# MPBoard_L2_Relay1_ext.net
KiCad netlist of a schematic drawn in Altium Designer
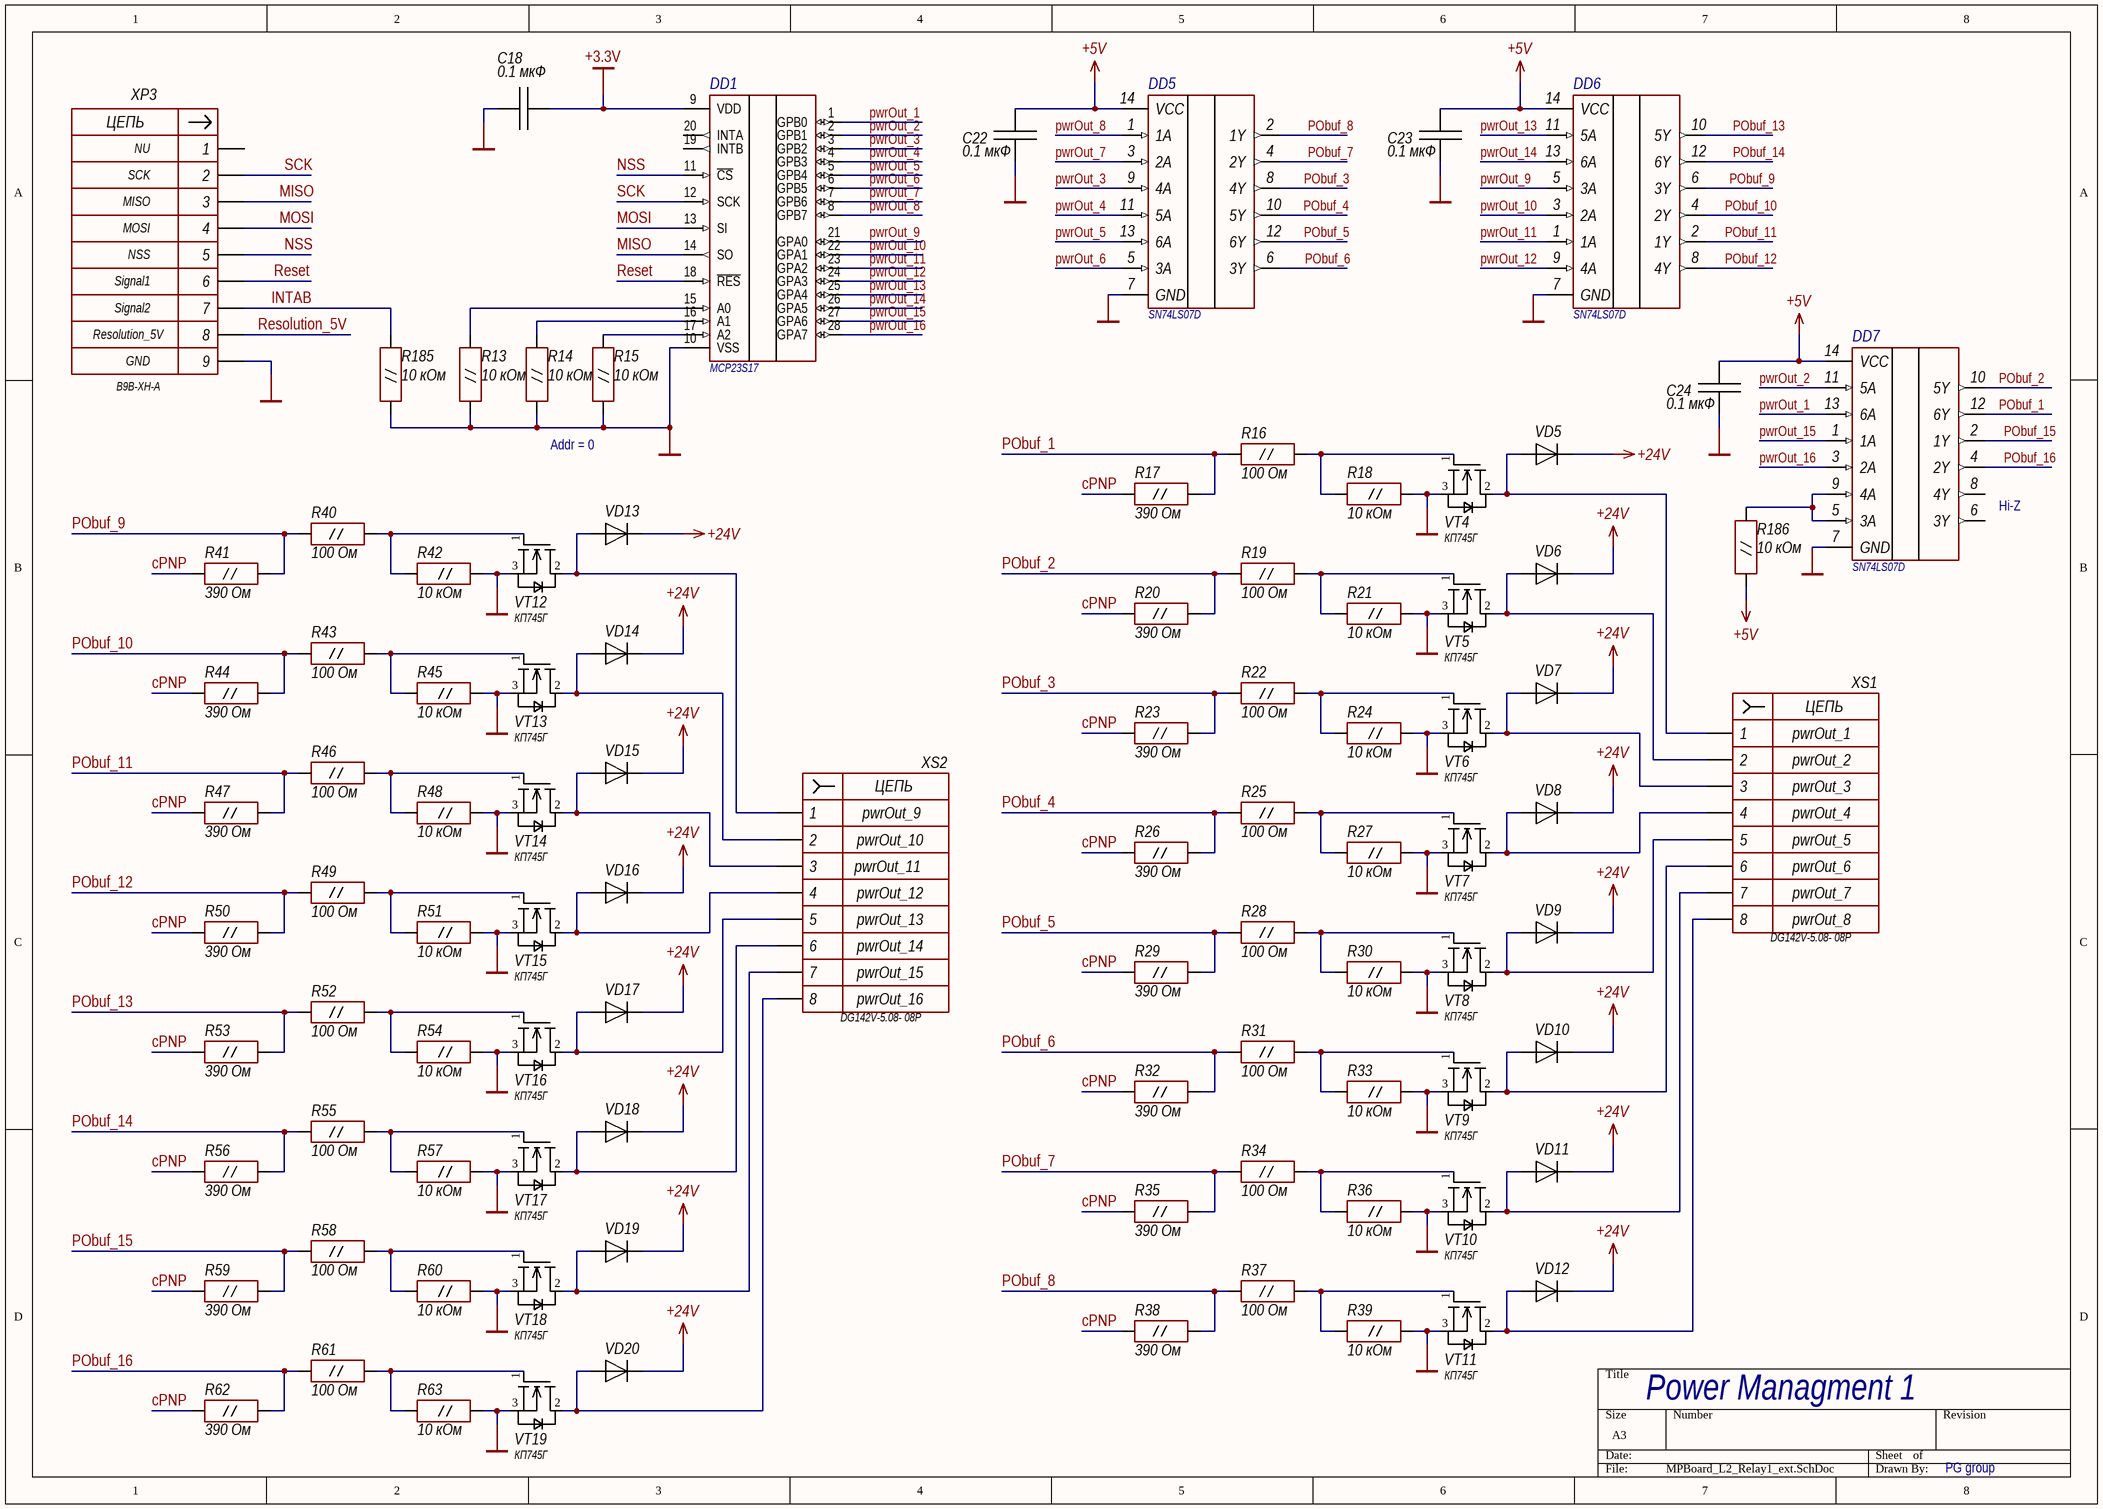
[diagram p0: MPBoard_L2_Relay1_ext.SchDoc]

(export (version "E")
  (design (tool "Eeschema 10.0.6"))
  (components
    (comp (ref "C18")
      (value "0.1 мкФ")
      (footprint "CAP-0603")
      (description "Конденсатор")
      (fields (field (name "MF") "KEMET") (field (name "TOLERANCE") "± 10 %"))
      (libsource (lib "MainBoard") (part "C"))
    )
    (comp (ref "C22")
      (value "0.1 мкФ")
      (footprint "CAP-0603")
      (description "Конденсатор")
      (fields (field (name "MF") "KEMET") (field (name "TOLERANCE") "± 10 %"))
      (libsource (lib "MainBoard") (part "C"))
    )
    (comp (ref "C23")
      (value "0.1 мкФ")
      (footprint "CAP-0603")
      (description "Конденсатор")
      (fields (field (name "MF") "KEMET") (field (name "TOLERANCE") "± 10 %"))
      (libsource (lib "MainBoard") (part "C"))
    )
    (comp (ref "C24")
      (value "0.1 мкФ")
      (footprint "CAP-0603")
      (description "Конденсатор")
      (fields (field (name "MF") "KEMET") (field (name "TOLERANCE") "± 10 %"))
      (libsource (lib "MainBoard") (part "C"))
    )
    (comp (ref "DD1")
      (value "MCP23S17")
      (footprint "SOIC-28")
      (description "I/O Expander 16 SPI")
      (fields (field (name "MF") "Microchip"))
      (libsource (lib "MPBoard") (part "DD_MCP23S17"))
    )
    (comp (ref "DD5")
      (value "SN74LS07D")
      (footprint "SOIC-14")
      (description "6-ch, 4.75_5.25V bipolar buffers with OC outputs")
      (fields (field (name "MF") "Texas Instruments"))
      (libsource (lib "MPBoard") (part "DD_SN74LS07D"))
    )
    (comp (ref "DD6")
      (value "SN74LS07D")
      (footprint "SOIC-14")
      (description "6-ch, 4.75_5.25V bipolar buffers with OC outputs")
      (fields (field (name "MF") "Texas Instruments"))
      (libsource (lib "") (part "DD_SN74LS07D_2"))
    )
    (comp (ref "DD7")
      (value "SN74LS07D")
      (footprint "SOIC-14")
      (description "6-ch, 4.75_5.25V bipolar buffers with OC outputs")
      (fields (field (name "MF") "Texas Instruments"))
      (libsource (lib "") (part "DD_SN74LS07D_1"))
    )
    (comp (ref "R13")
      (value "10 кОм")
      (footprint "RES-0603")
      (description "Резистор 0.1 W")
      (fields (field (name "MF") "Vishay") (field (name "TOLERANCE") "± 1 %"))
      (libsource (lib "") (part "R_0.125W_2"))
    )
    (comp (ref "R14")
      (value "10 кОм")
      (footprint "RES-0603")
      (description "Резистор 0.1 W")
      (fields (field (name "MF") "Vishay") (field (name "TOLERANCE") "± 1 %"))
      (libsource (lib "") (part "R_0.125W_2"))
    )
    (comp (ref "R15")
      (value "10 кОм")
      (footprint "RES-0603")
      (description "Резистор 0.1 W")
      (fields (field (name "MF") "Vishay") (field (name "TOLERANCE") "± 1 %"))
      (libsource (lib "") (part "R_0.125W_2"))
    )
    (comp (ref "R16")
      (value "100 Ом")
      (footprint "RES-0805")
      (description "Резистор 0.125 W")
      (fields (field (name "MF") "Vishay") (field (name "TOLERANCE") "± 1 %"))
      (libsource (lib "MainBoard") (part "R_0.125W"))
    )
    (comp (ref "R17")
      (value "390 Ом")
      (footprint "RES-0805")
      (description "Резистор 0.125 W")
      (fields (field (name "MF") "Vishay") (field (name "TOLERANCE") "± 1 %"))
      (libsource (lib "MainBoard") (part "R_0.125W"))
    )
    (comp (ref "R18")
      (value "10 кОм")
      (footprint "RES-0805")
      (description "Резистор 0.125 W")
      (fields (field (name "MF") "Vishay") (field (name "TOLERANCE") "± 1 %"))
      (libsource (lib "") (part "R_0.125W_1"))
    )
    (comp (ref "R19")
      (value "100 Ом")
      (footprint "RES-0805")
      (description "Резистор 0.125 W")
      (fields (field (name "MF") "Vishay") (field (name "TOLERANCE") "± 1 %"))
      (libsource (lib "MainBoard") (part "R_0.125W"))
    )
    (comp (ref "R20")
      (value "390 Ом")
      (footprint "RES-0805")
      (description "Резистор 0.125 W")
      (fields (field (name "MF") "Vishay") (field (name "TOLERANCE") "± 1 %"))
      (libsource (lib "MainBoard") (part "R_0.125W"))
    )
    (comp (ref "R21")
      (value "10 кОм")
      (footprint "RES-0805")
      (description "Резистор 0.125 W")
      (fields (field (name "MF") "Vishay") (field (name "TOLERANCE") "± 1 %"))
      (libsource (lib "") (part "R_0.125W_1"))
    )
    (comp (ref "R22")
      (value "100 Ом")
      (footprint "RES-0805")
      (description "Резистор 0.125 W")
      (fields (field (name "MF") "Vishay") (field (name "TOLERANCE") "± 1 %"))
      (libsource (lib "MainBoard") (part "R_0.125W"))
    )
    (comp (ref "R23")
      (value "390 Ом")
      (footprint "RES-0805")
      (description "Резистор 0.125 W")
      (fields (field (name "MF") "Vishay") (field (name "TOLERANCE") "± 1 %"))
      (libsource (lib "MainBoard") (part "R_0.125W"))
    )
    (comp (ref "R24")
      (value "10 кОм")
      (footprint "RES-0805")
      (description "Резистор 0.125 W")
      (fields (field (name "MF") "Vishay") (field (name "TOLERANCE") "± 1 %"))
      (libsource (lib "") (part "R_0.125W_1"))
    )
    (comp (ref "R25")
      (value "100 Ом")
      (footprint "RES-0805")
      (description "Резистор 0.125 W")
      (fields (field (name "MF") "Vishay") (field (name "TOLERANCE") "± 1 %"))
      (libsource (lib "MainBoard") (part "R_0.125W"))
    )
    (comp (ref "R26")
      (value "390 Ом")
      (footprint "RES-0805")
      (description "Резистор 0.125 W")
      (fields (field (name "MF") "Vishay") (field (name "TOLERANCE") "± 1 %"))
      (libsource (lib "MainBoard") (part "R_0.125W"))
    )
    (comp (ref "R27")
      (value "10 кОм")
      (footprint "RES-0805")
      (description "Резистор 0.125 W")
      (fields (field (name "MF") "Vishay") (field (name "TOLERANCE") "± 1 %"))
      (libsource (lib "") (part "R_0.125W_1"))
    )
    (comp (ref "R28")
      (value "100 Ом")
      (footprint "RES-0805")
      (description "Резистор 0.125 W")
      (fields (field (name "MF") "Vishay") (field (name "TOLERANCE") "± 1 %"))
      (libsource (lib "MainBoard") (part "R_0.125W"))
    )
    (comp (ref "R29")
      (value "390 Ом")
      (footprint "RES-0805")
      (description "Резистор 0.125 W")
      (fields (field (name "MF") "Vishay") (field (name "TOLERANCE") "± 1 %"))
      (libsource (lib "MainBoard") (part "R_0.125W"))
    )
    (comp (ref "R30")
      (value "10 кОм")
      (footprint "RES-0805")
      (description "Резистор 0.125 W")
      (fields (field (name "MF") "Vishay") (field (name "TOLERANCE") "± 1 %"))
      (libsource (lib "") (part "R_0.125W_1"))
    )
    (comp (ref "R31")
      (value "100 Ом")
      (footprint "RES-0805")
      (description "Резистор 0.125 W")
      (fields (field (name "MF") "Vishay") (field (name "TOLERANCE") "± 1 %"))
      (libsource (lib "MainBoard") (part "R_0.125W"))
    )
    (comp (ref "R32")
      (value "390 Ом")
      (footprint "RES-0805")
      (description "Резистор 0.125 W")
      (fields (field (name "MF") "Vishay") (field (name "TOLERANCE") "± 1 %"))
      (libsource (lib "MainBoard") (part "R_0.125W"))
    )
    (comp (ref "R33")
      (value "10 кОм")
      (footprint "RES-0805")
      (description "Резистор 0.125 W")
      (fields (field (name "MF") "Vishay") (field (name "TOLERANCE") "± 1 %"))
      (libsource (lib "") (part "R_0.125W_1"))
    )
    (comp (ref "R34")
      (value "100 Ом")
      (footprint "RES-0805")
      (description "Резистор 0.125 W")
      (fields (field (name "MF") "Vishay") (field (name "TOLERANCE") "± 1 %"))
      (libsource (lib "MainBoard") (part "R_0.125W"))
    )
    (comp (ref "R35")
      (value "390 Ом")
      (footprint "RES-0805")
      (description "Резистор 0.125 W")
      (fields (field (name "MF") "Vishay") (field (name "TOLERANCE") "± 1 %"))
      (libsource (lib "MainBoard") (part "R_0.125W"))
    )
    (comp (ref "R36")
      (value "10 кОм")
      (footprint "RES-0805")
      (description "Резистор 0.125 W")
      (fields (field (name "MF") "Vishay") (field (name "TOLERANCE") "± 1 %"))
      (libsource (lib "") (part "R_0.125W_1"))
    )
    (comp (ref "R37")
      (value "100 Ом")
      (footprint "RES-0805")
      (description "Резистор 0.125 W")
      (fields (field (name "MF") "Vishay") (field (name "TOLERANCE") "± 1 %"))
      (libsource (lib "MainBoard") (part "R_0.125W"))
    )
    (comp (ref "R38")
      (value "390 Ом")
      (footprint "RES-0805")
      (description "Резистор 0.125 W")
      (fields (field (name "MF") "Vishay") (field (name "TOLERANCE") "± 1 %"))
      (libsource (lib "MainBoard") (part "R_0.125W"))
    )
    (comp (ref "R39")
      (value "10 кОм")
      (footprint "RES-0805")
      (description "Резистор 0.125 W")
      (fields (field (name "MF") "Vishay") (field (name "TOLERANCE") "± 1 %"))
      (libsource (lib "") (part "R_0.125W_1"))
    )
    (comp (ref "R40")
      (value "100 Ом")
      (footprint "RES-0805")
      (description "Резистор 0.125 W")
      (fields (field (name "MF") "Vishay") (field (name "TOLERANCE") "± 1 %"))
      (libsource (lib "MainBoard") (part "R_0.125W"))
    )
    (comp (ref "R41")
      (value "390 Ом")
      (footprint "RES-0805")
      (description "Резистор 0.125 W")
      (fields (field (name "MF") "Vishay") (field (name "TOLERANCE") "± 1 %"))
      (libsource (lib "MainBoard") (part "R_0.125W"))
    )
    (comp (ref "R42")
      (value "10 кОм")
      (footprint "RES-0805")
      (description "Резистор 0.125 W")
      (fields (field (name "MF") "Vishay") (field (name "TOLERANCE") "± 1 %"))
      (libsource (lib "") (part "R_0.125W_1"))
    )
    (comp (ref "R43")
      (value "100 Ом")
      (footprint "RES-0805")
      (description "Резистор 0.125 W")
      (fields (field (name "MF") "Vishay") (field (name "TOLERANCE") "± 1 %"))
      (libsource (lib "MainBoard") (part "R_0.125W"))
    )
    (comp (ref "R44")
      (value "390 Ом")
      (footprint "RES-0805")
      (description "Резистор 0.125 W")
      (fields (field (name "MF") "Vishay") (field (name "TOLERANCE") "± 1 %"))
      (libsource (lib "MainBoard") (part "R_0.125W"))
    )
    (comp (ref "R45")
      (value "10 кОм")
      (footprint "RES-0805")
      (description "Резистор 0.125 W")
      (fields (field (name "MF") "Vishay") (field (name "TOLERANCE") "± 1 %"))
      (libsource (lib "") (part "R_0.125W_1"))
    )
    (comp (ref "R46")
      (value "100 Ом")
      (footprint "RES-0805")
      (description "Резистор 0.125 W")
      (fields (field (name "MF") "Vishay") (field (name "TOLERANCE") "± 1 %"))
      (libsource (lib "MainBoard") (part "R_0.125W"))
    )
    (comp (ref "R47")
      (value "390 Ом")
      (footprint "RES-0805")
      (description "Резистор 0.125 W")
      (fields (field (name "MF") "Vishay") (field (name "TOLERANCE") "± 1 %"))
      (libsource (lib "MainBoard") (part "R_0.125W"))
    )
    (comp (ref "R48")
      (value "10 кОм")
      (footprint "RES-0805")
      (description "Резистор 0.125 W")
      (fields (field (name "MF") "Vishay") (field (name "TOLERANCE") "± 1 %"))
      (libsource (lib "") (part "R_0.125W_1"))
    )
    (comp (ref "R49")
      (value "100 Ом")
      (footprint "RES-0805")
      (description "Резистор 0.125 W")
      (fields (field (name "MF") "Vishay") (field (name "TOLERANCE") "± 1 %"))
      (libsource (lib "MainBoard") (part "R_0.125W"))
    )
    (comp (ref "R50")
      (value "390 Ом")
      (footprint "RES-0805")
      (description "Резистор 0.125 W")
      (fields (field (name "MF") "Vishay") (field (name "TOLERANCE") "± 1 %"))
      (libsource (lib "MainBoard") (part "R_0.125W"))
    )
    (comp (ref "R51")
      (value "10 кОм")
      (footprint "RES-0805")
      (description "Резистор 0.125 W")
      (fields (field (name "MF") "Vishay") (field (name "TOLERANCE") "± 1 %"))
      (libsource (lib "") (part "R_0.125W_1"))
    )
    (comp (ref "R52")
      (value "100 Ом")
      (footprint "RES-0805")
      (description "Резистор 0.125 W")
      (fields (field (name "MF") "Vishay") (field (name "TOLERANCE") "± 1 %"))
      (libsource (lib "MainBoard") (part "R_0.125W"))
    )
    (comp (ref "R53")
      (value "390 Ом")
      (footprint "RES-0805")
      (description "Резистор 0.125 W")
      (fields (field (name "MF") "Vishay") (field (name "TOLERANCE") "± 1 %"))
      (libsource (lib "MainBoard") (part "R_0.125W"))
    )
    (comp (ref "R54")
      (value "10 кОм")
      (footprint "RES-0805")
      (description "Резистор 0.125 W")
      (fields (field (name "MF") "Vishay") (field (name "TOLERANCE") "± 1 %"))
      (libsource (lib "") (part "R_0.125W_1"))
    )
    (comp (ref "R55")
      (value "100 Ом")
      (footprint "RES-0805")
      (description "Резистор 0.125 W")
      (fields (field (name "MF") "Vishay") (field (name "TOLERANCE") "± 1 %"))
      (libsource (lib "MainBoard") (part "R_0.125W"))
    )
    (comp (ref "R56")
      (value "390 Ом")
      (footprint "RES-0805")
      (description "Резистор 0.125 W")
      (fields (field (name "MF") "Vishay") (field (name "TOLERANCE") "± 1 %"))
      (libsource (lib "MainBoard") (part "R_0.125W"))
    )
    (comp (ref "R57")
      (value "10 кОм")
      (footprint "RES-0805")
      (description "Резистор 0.125 W")
      (fields (field (name "MF") "Vishay") (field (name "TOLERANCE") "± 1 %"))
      (libsource (lib "") (part "R_0.125W_1"))
    )
    (comp (ref "R58")
      (value "100 Ом")
      (footprint "RES-0805")
      (description "Резистор 0.125 W")
      (fields (field (name "MF") "Vishay") (field (name "TOLERANCE") "± 1 %"))
      (libsource (lib "MainBoard") (part "R_0.125W"))
    )
    (comp (ref "R59")
      (value "390 Ом")
      (footprint "RES-0805")
      (description "Резистор 0.125 W")
      (fields (field (name "MF") "Vishay") (field (name "TOLERANCE") "± 1 %"))
      (libsource (lib "MainBoard") (part "R_0.125W"))
    )
    (comp (ref "R60")
      (value "10 кОм")
      (footprint "RES-0805")
      (description "Резистор 0.125 W")
      (fields (field (name "MF") "Vishay") (field (name "TOLERANCE") "± 1 %"))
      (libsource (lib "") (part "R_0.125W_1"))
    )
    (comp (ref "R61")
      (value "100 Ом")
      (footprint "RES-0805")
      (description "Резистор 0.125 W")
      (fields (field (name "MF") "Vishay") (field (name "TOLERANCE") "± 1 %"))
      (libsource (lib "MainBoard") (part "R_0.125W"))
    )
    (comp (ref "R62")
      (value "390 Ом")
      (footprint "RES-0805")
      (description "Резистор 0.125 W")
      (fields (field (name "MF") "Vishay") (field (name "TOLERANCE") "± 1 %"))
      (libsource (lib "MainBoard") (part "R_0.125W"))
    )
    (comp (ref "R63")
      (value "10 кОм")
      (footprint "RES-0805")
      (description "Резистор 0.125 W")
      (fields (field (name "MF") "Vishay") (field (name "TOLERANCE") "± 1 %"))
      (libsource (lib "") (part "R_0.125W_1"))
    )
    (comp (ref "R185")
      (value "10 кОм")
      (footprint "RES-0603")
      (description "Резистор 0.1 W")
      (fields (field (name "MF") "Vishay") (field (name "TOLERANCE") "± 1 %"))
      (libsource (lib "") (part "R_0.125W_2"))
    )
    (comp (ref "R186")
      (value "10 кОм")
      (footprint "RES-0603")
      (description "Резистор 0.1 W")
      (fields (field (name "MF") "Vishay") (field (name "TOLERANCE") "± 1 %"))
      (libsource (lib "") (part "R_0.125W_2"))
    )
    (comp (ref "VD5")
      (value "HER108")
      (footprint "DIOD-MILS-400")
      (description "Диод Выпрямительный")
      (fields (field (name "MF") "Taiwan Semiconductor") (field (name "MFPARTNUM") "HER108G"))
      (libsource (lib "MainBoard") (part "VD"))
    )
    (comp (ref "VD6")
      (value "HER108")
      (footprint "DIOD-MILS-400")
      (description "Диод Выпрямительный")
      (fields (field (name "MF") "Taiwan Semiconductor") (field (name "MFPARTNUM") "HER108G"))
      (libsource (lib "MainBoard") (part "VD"))
    )
    (comp (ref "VD7")
      (value "HER108")
      (footprint "DIOD-MILS-400")
      (description "Диод Выпрямительный")
      (fields (field (name "MF") "Taiwan Semiconductor") (field (name "MFPARTNUM") "HER108G"))
      (libsource (lib "MainBoard") (part "VD"))
    )
    (comp (ref "VD8")
      (value "HER108")
      (footprint "DIOD-MILS-400")
      (description "Диод Выпрямительный")
      (fields (field (name "MF") "Taiwan Semiconductor") (field (name "MFPARTNUM") "HER108G"))
      (libsource (lib "MainBoard") (part "VD"))
    )
    (comp (ref "VD9")
      (value "HER108")
      (footprint "DIOD-MILS-400")
      (description "Диод Выпрямительный")
      (fields (field (name "MF") "Taiwan Semiconductor") (field (name "MFPARTNUM") "HER108G"))
      (libsource (lib "MainBoard") (part "VD"))
    )
    (comp (ref "VD10")
      (value "HER108")
      (footprint "DIOD-MILS-400")
      (description "Диод Выпрямительный")
      (fields (field (name "MF") "Taiwan Semiconductor") (field (name "MFPARTNUM") "HER108G"))
      (libsource (lib "MainBoard") (part "VD"))
    )
    (comp (ref "VD11")
      (value "HER108")
      (footprint "DIOD-MILS-400")
      (description "Диод Выпрямительный")
      (fields (field (name "MF") "Taiwan Semiconductor") (field (name "MFPARTNUM") "HER108G"))
      (libsource (lib "MainBoard") (part "VD"))
    )
    (comp (ref "VD12")
      (value "HER108")
      (footprint "DIOD-MILS-400")
      (description "Диод Выпрямительный")
      (fields (field (name "MF") "Taiwan Semiconductor") (field (name "MFPARTNUM") "HER108G"))
      (libsource (lib "MainBoard") (part "VD"))
    )
    (comp (ref "VD13")
      (value "HER108")
      (footprint "DIOD-MILS-400")
      (description "Диод Выпрямительный")
      (fields (field (name "MF") "Taiwan Semiconductor") (field (name "MFPARTNUM") "HER108G"))
      (libsource (lib "MainBoard") (part "VD"))
    )
    (comp (ref "VD14")
      (value "HER108")
      (footprint "DIOD-MILS-400")
      (description "Диод Выпрямительный")
      (fields (field (name "MF") "Taiwan Semiconductor") (field (name "MFPARTNUM") "HER108G"))
      (libsource (lib "MainBoard") (part "VD"))
    )
    (comp (ref "VD15")
      (value "HER108")
      (footprint "DIOD-MILS-400")
      (description "Диод Выпрямительный")
      (fields (field (name "MF") "Taiwan Semiconductor") (field (name "MFPARTNUM") "HER108G"))
      (libsource (lib "MainBoard") (part "VD"))
    )
    (comp (ref "VD16")
      (value "HER108")
      (footprint "DIOD-MILS-400")
      (description "Диод Выпрямительный")
      (fields (field (name "MF") "Taiwan Semiconductor") (field (name "MFPARTNUM") "HER108G"))
      (libsource (lib "MainBoard") (part "VD"))
    )
    (comp (ref "VD17")
      (value "HER108")
      (footprint "DIOD-MILS-400")
      (description "Диод Выпрямительный")
      (fields (field (name "MF") "Taiwan Semiconductor") (field (name "MFPARTNUM") "HER108G"))
      (libsource (lib "MainBoard") (part "VD"))
    )
    (comp (ref "VD18")
      (value "HER108")
      (footprint "DIOD-MILS-400")
      (description "Диод Выпрямительный")
      (fields (field (name "MF") "Taiwan Semiconductor") (field (name "MFPARTNUM") "HER108G"))
      (libsource (lib "MainBoard") (part "VD"))
    )
    (comp (ref "VD19")
      (value "HER108")
      (footprint "DIOD-MILS-400")
      (description "Диод Выпрямительный")
      (fields (field (name "MF") "Taiwan Semiconductor") (field (name "MFPARTNUM") "HER108G"))
      (libsource (lib "MainBoard") (part "VD"))
    )
    (comp (ref "VD20")
      (value "HER108")
      (footprint "DIOD-MILS-400")
      (description "Диод Выпрямительный")
      (fields (field (name "MF") "Taiwan Semiconductor") (field (name "MFPARTNUM") "HER108G"))
      (libsource (lib "MainBoard") (part "VD"))
    )
    (comp (ref "VT4")
      (value "КП745Г")
      (footprint "TO220S inline")
      (description "MOSFET")
      (fields (field (name "MF") "Интеграл") (field (name "VOLTAGE") "100 В"))
      (libsource (lib "MPBoard") (part "VT_N-MOSFET"))
    )
    (comp (ref "VT5")
      (value "КП745Г")
      (footprint "TO220S inline")
      (description "MOSFET")
      (fields (field (name "MF") "Интеграл") (field (name "VOLTAGE") "100 В"))
      (libsource (lib "MPBoard") (part "VT_N-MOSFET"))
    )
    (comp (ref "VT6")
      (value "КП745Г")
      (footprint "TO220S inline")
      (description "MOSFET")
      (fields (field (name "MF") "Интеграл") (field (name "VOLTAGE") "100 В"))
      (libsource (lib "MPBoard") (part "VT_N-MOSFET"))
    )
    (comp (ref "VT7")
      (value "КП745Г")
      (footprint "TO220S inline")
      (description "MOSFET")
      (fields (field (name "MF") "Интеграл") (field (name "VOLTAGE") "100 В"))
      (libsource (lib "MPBoard") (part "VT_N-MOSFET"))
    )
    (comp (ref "VT8")
      (value "КП745Г")
      (footprint "TO220S inline")
      (description "MOSFET")
      (fields (field (name "MF") "Интеграл") (field (name "VOLTAGE") "100 В"))
      (libsource (lib "MPBoard") (part "VT_N-MOSFET"))
    )
    (comp (ref "VT9")
      (value "КП745Г")
      (footprint "TO220S inline")
      (description "MOSFET")
      (fields (field (name "MF") "Интеграл") (field (name "VOLTAGE") "100 В"))
      (libsource (lib "MPBoard") (part "VT_N-MOSFET"))
    )
    (comp (ref "VT10")
      (value "КП745Г")
      (footprint "TO220S inline")
      (description "MOSFET")
      (fields (field (name "MF") "Интеграл") (field (name "VOLTAGE") "100 В"))
      (libsource (lib "MPBoard") (part "VT_N-MOSFET"))
    )
    (comp (ref "VT11")
      (value "КП745Г")
      (footprint "TO220S inline")
      (description "MOSFET")
      (fields (field (name "MF") "Интеграл") (field (name "VOLTAGE") "100 В"))
      (libsource (lib "MPBoard") (part "VT_N-MOSFET"))
    )
    (comp (ref "VT12")
      (value "КП745Г")
      (footprint "TO220S inline")
      (description "MOSFET")
      (fields (field (name "MF") "Интеграл") (field (name "VOLTAGE") "100 В"))
      (libsource (lib "MPBoard") (part "VT_N-MOSFET"))
    )
    (comp (ref "VT13")
      (value "КП745Г")
      (footprint "TO220S inline")
      (description "MOSFET")
      (fields (field (name "MF") "Интеграл") (field (name "VOLTAGE") "100 В"))
      (libsource (lib "MPBoard") (part "VT_N-MOSFET"))
    )
    (comp (ref "VT14")
      (value "КП745Г")
      (footprint "TO220S inline")
      (description "MOSFET")
      (fields (field (name "MF") "Интеграл") (field (name "VOLTAGE") "100 В"))
      (libsource (lib "MPBoard") (part "VT_N-MOSFET"))
    )
    (comp (ref "VT15")
      (value "КП745Г")
      (footprint "TO220S inline")
      (description "MOSFET")
      (fields (field (name "MF") "Интеграл") (field (name "VOLTAGE") "100 В"))
      (libsource (lib "MPBoard") (part "VT_N-MOSFET"))
    )
    (comp (ref "VT16")
      (value "КП745Г")
      (footprint "TO220S inline")
      (description "MOSFET")
      (fields (field (name "MF") "Интеграл") (field (name "VOLTAGE") "100 В"))
      (libsource (lib "MPBoard") (part "VT_N-MOSFET"))
    )
    (comp (ref "VT17")
      (value "КП745Г")
      (footprint "TO220S inline")
      (description "MOSFET")
      (fields (field (name "MF") "Интеграл") (field (name "VOLTAGE") "100 В"))
      (libsource (lib "MPBoard") (part "VT_N-MOSFET"))
    )
    (comp (ref "VT18")
      (value "КП745Г")
      (footprint "TO220S inline")
      (description "MOSFET")
      (fields (field (name "MF") "Интеграл") (field (name "VOLTAGE") "100 В"))
      (libsource (lib "MPBoard") (part "VT_N-MOSFET"))
    )
    (comp (ref "VT19")
      (value "КП745Г")
      (footprint "TO220S inline")
      (description "MOSFET")
      (fields (field (name "MF") "Интеграл") (field (name "VOLTAGE") "100 В"))
      (libsource (lib "MPBoard") (part "VT_N-MOSFET"))
    )
    (comp (ref "XP3")
      (value "B9B-XH-A")
      (footprint "JST-B9B-XH-A")
      (description "вилка 9 контактов")
      (fields
        (field (name "MF") "JST Corporation")
        (field (name "NET9") "GND")
        (field (name "NET8") "Resolution_5V")
        (field (name "NET7") "Signal2")
        (field (name "NET6") "Signal1")
        (field (name "NET5") "MOSI")
        (field (name "NET1") "NU")
        (field (name "NET2") "NSS")
        (field (name "NET3") "SCK")
        (field (name "NET4") "MISO")
      )
      (libsource (lib "MPBoard") (part "XP9"))
    )
    (comp (ref "XS1")
      (value "DG142V-5.08- 08P")
      (footprint "DG142V-5.08-08")
      (description "розетка 8 контактов")
      (fields
        (field (name "MF") "Degson Electronics")
        (field (name "MFPARTNUM") "DG142V-5.08- 08P-14-00A(H)")
        (field (name "NET6") "pwrOut_6")
        (field (name "NET5") "pwrOut_5")
        (field (name "NET1") "pwrOut_1")
        (field (name "NET2") "pwrOut_2")
        (field (name "NET3") "pwrOut_3")
        (field (name "NET4") "pwrOut_4")
        (field (name "NET7") "pwrOut_7")
        (field (name "NET8") "pwrOut_8")
      )
      (libsource (lib "MPBoard") (part "XS8"))
    )
    (comp (ref "XS2")
      (value "DG142V-5.08- 08P")
      (footprint "DG142V-5.08-08")
      (description "розетка 8 контактов")
      (fields
        (field (name "MF") "Degson Electronics")
        (field (name "MFPARTNUM") "DG142V-5.08- 08P-14-00A(H)")
        (field (name "NET6") "pwrOut_14")
        (field (name "NET5") "pwrOut_13")
        (field (name "NET1") "pwrOut_9")
        (field (name "NET2") "pwrOut_10")
        (field (name "NET3") "pwrOut_11")
        (field (name "NET4") "pwrOut_12")
        (field (name "NET7") "pwrOut_15")
        (field (name "NET8") "pwrOut_16")
      )
      (libsource (lib "MPBoard") (part "XS8"))
    )
  )
  (nets
    (net (code "1") (name "+3.3V") (class "Default")
      (node (ref "C18") (pin "2") (pinfunction "2_2") (pintype "passive"))
      (node (ref "DD1") (pin "9") (pinfunction "VDD_9") (pintype "power_in"))
    )
    (net (code "2") (name "+5V") (class "Default")
      (node (ref "C22") (pin "2") (pinfunction "2_2") (pintype "passive"))
      (node (ref "C23") (pin "2") (pinfunction "2_2") (pintype "passive"))
      (node (ref "C24") (pin "2") (pinfunction "2_2") (pintype "passive"))
      (node (ref "DD5") (pin "14") (pinfunction "VCC_14") (pintype "power_in"))
      (node (ref "DD6") (pin "14") (pinfunction "VCC_14") (pintype "power_in"))
      (node (ref "DD7") (pin "14") (pinfunction "VCC_14") (pintype "power_in"))
      (node (ref "R186") (pin "1") (pinfunction "1_1") (pintype "passive"))
    )
    (net (code "3") (name "+24V") (class "Default")
      (node (ref "VD10") (pin "2") (pinfunction "2_2") (pintype "passive"))
      (node (ref "VD11") (pin "2") (pinfunction "2_2") (pintype "passive"))
      (node (ref "VD12") (pin "2") (pinfunction "2_2") (pintype "passive"))
      (node (ref "VD13") (pin "2") (pinfunction "2_2") (pintype "passive"))
      (node (ref "VD14") (pin "2") (pinfunction "2_2") (pintype "passive"))
      (node (ref "VD15") (pin "2") (pinfunction "2_2") (pintype "passive"))
      (node (ref "VD16") (pin "2") (pinfunction "2_2") (pintype "passive"))
      (node (ref "VD17") (pin "2") (pinfunction "2_2") (pintype "passive"))
      (node (ref "VD18") (pin "2") (pinfunction "2_2") (pintype "passive"))
      (node (ref "VD19") (pin "2") (pinfunction "2_2") (pintype "passive"))
      (node (ref "VD20") (pin "2") (pinfunction "2_2") (pintype "passive"))
      (node (ref "VD5") (pin "2") (pinfunction "2_2") (pintype "passive"))
      (node (ref "VD6") (pin "2") (pinfunction "2_2") (pintype "passive"))
      (node (ref "VD7") (pin "2") (pinfunction "2_2") (pintype "passive"))
      (node (ref "VD8") (pin "2") (pinfunction "2_2") (pintype "passive"))
      (node (ref "VD9") (pin "2") (pinfunction "2_2") (pintype "passive"))
    )
    (net (code "4") (name "/INTAB") (class "Default")
      (node (ref "R185") (pin "2") (pinfunction "2_2") (pintype "passive"))
      (node (ref "XP3") (pin "7") (pinfunction "7_7") (pintype "passive"))
    )
    (net (code "5") (name "/MISO") (class "Default")
      (node (ref "DD1") (pin "14") (pinfunction "SO_14") (pintype "output"))
      (node (ref "XP3") (pin "3") (pinfunction "3_3") (pintype "passive"))
    )
    (net (code "6") (name "/MOSI") (class "Default")
      (node (ref "DD1") (pin "13") (pinfunction "SI_13") (pintype "input"))
      (node (ref "XP3") (pin "4") (pinfunction "4_4") (pintype "passive"))
    )
    (net (code "7") (name "/NSS") (class "Default")
      (node (ref "DD1") (pin "11") (pinfunction "~{CS}_11") (pintype "input"))
      (node (ref "XP3") (pin "5") (pinfunction "5_5") (pintype "passive"))
    )
    (net (code "8") (name "/PObuf_1") (class "Default")
      (node (ref "DD7") (pin "12") (pinfunction "6Y_12") (pintype "output"))
      (node (ref "R16") (pin "1") (pinfunction "1_1") (pintype "passive"))
      (node (ref "R17") (pin "2") (pinfunction "2_2") (pintype "passive"))
    )
    (net (code "9") (name "/PObuf_2") (class "Default")
      (node (ref "DD7") (pin "10") (pinfunction "5Y_10") (pintype "output"))
      (node (ref "R19") (pin "1") (pinfunction "1_1") (pintype "passive"))
      (node (ref "R20") (pin "2") (pinfunction "2_2") (pintype "passive"))
    )
    (net (code "10") (name "/PObuf_3") (class "Default")
      (node (ref "DD5") (pin "8") (pinfunction "4Y_8") (pintype "output"))
      (node (ref "R22") (pin "1") (pinfunction "1_1") (pintype "passive"))
      (node (ref "R23") (pin "2") (pinfunction "2_2") (pintype "passive"))
    )
    (net (code "11") (name "/PObuf_4") (class "Default")
      (node (ref "DD5") (pin "10") (pinfunction "5Y_10") (pintype "output"))
      (node (ref "R25") (pin "1") (pinfunction "1_1") (pintype "passive"))
      (node (ref "R26") (pin "2") (pinfunction "2_2") (pintype "passive"))
    )
    (net (code "12") (name "/PObuf_5") (class "Default")
      (node (ref "DD5") (pin "12") (pinfunction "6Y_12") (pintype "output"))
      (node (ref "R28") (pin "1") (pinfunction "1_1") (pintype "passive"))
      (node (ref "R29") (pin "2") (pinfunction "2_2") (pintype "passive"))
    )
    (net (code "13") (name "/PObuf_6") (class "Default")
      (node (ref "DD5") (pin "6") (pinfunction "3Y_6") (pintype "output"))
      (node (ref "R31") (pin "1") (pinfunction "1_1") (pintype "passive"))
      (node (ref "R32") (pin "2") (pinfunction "2_2") (pintype "passive"))
    )
    (net (code "14") (name "/PObuf_7") (class "Default")
      (node (ref "DD5") (pin "4") (pinfunction "2Y_4") (pintype "output"))
      (node (ref "R34") (pin "1") (pinfunction "1_1") (pintype "passive"))
      (node (ref "R35") (pin "2") (pinfunction "2_2") (pintype "passive"))
    )
    (net (code "15") (name "/PObuf_8") (class "Default")
      (node (ref "DD5") (pin "2") (pinfunction "1Y_2") (pintype "output"))
      (node (ref "R37") (pin "1") (pinfunction "1_1") (pintype "passive"))
      (node (ref "R38") (pin "2") (pinfunction "2_2") (pintype "passive"))
    )
    (net (code "16") (name "/PObuf_9") (class "Default")
      (node (ref "DD6") (pin "6") (pinfunction "3Y_6") (pintype "output"))
      (node (ref "R40") (pin "1") (pinfunction "1_1") (pintype "passive"))
      (node (ref "R41") (pin "2") (pinfunction "2_2") (pintype "passive"))
    )
    (net (code "17") (name "/PObuf_10") (class "Default")
      (node (ref "DD6") (pin "4") (pinfunction "2Y_4") (pintype "output"))
      (node (ref "R43") (pin "1") (pinfunction "1_1") (pintype "passive"))
      (node (ref "R44") (pin "2") (pinfunction "2_2") (pintype "passive"))
    )
    (net (code "18") (name "/PObuf_11") (class "Default")
      (node (ref "DD6") (pin "2") (pinfunction "1Y_2") (pintype "output"))
      (node (ref "R46") (pin "1") (pinfunction "1_1") (pintype "passive"))
      (node (ref "R47") (pin "2") (pinfunction "2_2") (pintype "passive"))
    )
    (net (code "19") (name "/PObuf_12") (class "Default")
      (node (ref "DD6") (pin "8") (pinfunction "4Y_8") (pintype "output"))
      (node (ref "R49") (pin "1") (pinfunction "1_1") (pintype "passive"))
      (node (ref "R50") (pin "2") (pinfunction "2_2") (pintype "passive"))
    )
    (net (code "20") (name "/PObuf_13") (class "Default")
      (node (ref "DD6") (pin "10") (pinfunction "5Y_10") (pintype "output"))
      (node (ref "R52") (pin "1") (pinfunction "1_1") (pintype "passive"))
      (node (ref "R53") (pin "2") (pinfunction "2_2") (pintype "passive"))
    )
    (net (code "21") (name "/PObuf_14") (class "Default")
      (node (ref "DD6") (pin "12") (pinfunction "6Y_12") (pintype "output"))
      (node (ref "R55") (pin "1") (pinfunction "1_1") (pintype "passive"))
      (node (ref "R56") (pin "2") (pinfunction "2_2") (pintype "passive"))
    )
    (net (code "22") (name "/PObuf_15") (class "Default")
      (node (ref "DD7") (pin "2") (pinfunction "1Y_2") (pintype "output"))
      (node (ref "R58") (pin "1") (pinfunction "1_1") (pintype "passive"))
      (node (ref "R59") (pin "2") (pinfunction "2_2") (pintype "passive"))
    )
    (net (code "23") (name "/PObuf_16") (class "Default")
      (node (ref "DD7") (pin "4") (pinfunction "2Y_4") (pintype "output"))
      (node (ref "R61") (pin "1") (pinfunction "1_1") (pintype "passive"))
      (node (ref "R62") (pin "2") (pinfunction "2_2") (pintype "passive"))
    )
    (net (code "24") (name "/Reset") (class "Default")
      (node (ref "DD1") (pin "18") (pinfunction "~{RES}_18") (pintype "input"))
      (node (ref "XP3") (pin "6") (pinfunction "6_6") (pintype "passive"))
    )
    (net (code "25") (name "/Resolution_5V") (class "Default")
      (node (ref "XP3") (pin "8") (pinfunction "8_8") (pintype "passive"))
    )
    (net (code "26") (name "/SCK") (class "Default")
      (node (ref "DD1") (pin "12") (pinfunction "SCK_12") (pintype "input"))
      (node (ref "XP3") (pin "2") (pinfunction "2_2") (pintype "passive"))
    )
    (net (code "27") (name "/cPNP") (class "Default")
      (node (ref "R17") (pin "1") (pinfunction "1_1") (pintype "passive"))
      (node (ref "R20") (pin "1") (pinfunction "1_1") (pintype "passive"))
      (node (ref "R23") (pin "1") (pinfunction "1_1") (pintype "passive"))
      (node (ref "R26") (pin "1") (pinfunction "1_1") (pintype "passive"))
      (node (ref "R29") (pin "1") (pinfunction "1_1") (pintype "passive"))
      (node (ref "R32") (pin "1") (pinfunction "1_1") (pintype "passive"))
      (node (ref "R35") (pin "1") (pinfunction "1_1") (pintype "passive"))
      (node (ref "R38") (pin "1") (pinfunction "1_1") (pintype "passive"))
      (node (ref "R41") (pin "1") (pinfunction "1_1") (pintype "passive"))
      (node (ref "R44") (pin "1") (pinfunction "1_1") (pintype "passive"))
      (node (ref "R47") (pin "1") (pinfunction "1_1") (pintype "passive"))
      (node (ref "R50") (pin "1") (pinfunction "1_1") (pintype "passive"))
      (node (ref "R53") (pin "1") (pinfunction "1_1") (pintype "passive"))
      (node (ref "R56") (pin "1") (pinfunction "1_1") (pintype "passive"))
      (node (ref "R59") (pin "1") (pinfunction "1_1") (pintype "passive"))
      (node (ref "R62") (pin "1") (pinfunction "1_1") (pintype "passive"))
    )
    (net (code "28") (name "/pwrOut_1") (class "Default")
      (node (ref "DD1") (pin "1") (pinfunction "GPB0_1") (pintype "bidirectional"))
      (node (ref "DD7") (pin "13") (pinfunction "6A_13") (pintype "input"))
    )
    (net (code "29") (name "/pwrOut_2") (class "Default")
      (node (ref "DD1") (pin "2") (pinfunction "GPB1_2") (pintype "bidirectional"))
      (node (ref "DD7") (pin "11") (pinfunction "5A_11") (pintype "input"))
    )
    (net (code "30") (name "/pwrOut_3") (class "Default")
      (node (ref "DD1") (pin "3") (pinfunction "GPB2_3") (pintype "bidirectional"))
      (node (ref "DD5") (pin "9") (pinfunction "4A_9") (pintype "input"))
    )
    (net (code "31") (name "/pwrOut_4") (class "Default")
      (node (ref "DD1") (pin "4") (pinfunction "GPB3_4") (pintype "bidirectional"))
      (node (ref "DD5") (pin "11") (pinfunction "5A_11") (pintype "input"))
    )
    (net (code "32") (name "/pwrOut_5") (class "Default")
      (node (ref "DD1") (pin "5") (pinfunction "GPB4_5") (pintype "bidirectional"))
      (node (ref "DD5") (pin "13") (pinfunction "6A_13") (pintype "input"))
    )
    (net (code "33") (name "/pwrOut_6") (class "Default")
      (node (ref "DD1") (pin "6") (pinfunction "GPB5_6") (pintype "bidirectional"))
      (node (ref "DD5") (pin "5") (pinfunction "3A_5") (pintype "input"))
    )
    (net (code "34") (name "/pwrOut_7") (class "Default")
      (node (ref "DD1") (pin "7") (pinfunction "GPB6_7") (pintype "bidirectional"))
      (node (ref "DD5") (pin "3") (pinfunction "2A_3") (pintype "input"))
    )
    (net (code "35") (name "/pwrOut_8") (class "Default")
      (node (ref "DD1") (pin "8") (pinfunction "GPB7_8") (pintype "bidirectional"))
      (node (ref "DD5") (pin "1") (pinfunction "1A_1") (pintype "input"))
    )
    (net (code "36") (name "/pwrOut_9") (class "Default")
      (node (ref "DD1") (pin "21") (pinfunction "GPA0_21") (pintype "bidirectional"))
      (node (ref "DD6") (pin "5") (pinfunction "3A_5") (pintype "input"))
    )
    (net (code "37") (name "/pwrOut_10") (class "Default")
      (node (ref "DD1") (pin "22") (pinfunction "GPA1_22") (pintype "bidirectional"))
      (node (ref "DD6") (pin "3") (pinfunction "2A_3") (pintype "input"))
    )
    (net (code "38") (name "/pwrOut_11") (class "Default")
      (node (ref "DD1") (pin "23") (pinfunction "GPA2_23") (pintype "bidirectional"))
      (node (ref "DD6") (pin "1") (pinfunction "1A_1") (pintype "input"))
    )
    (net (code "39") (name "/pwrOut_12") (class "Default")
      (node (ref "DD1") (pin "24") (pinfunction "GPA3_24") (pintype "bidirectional"))
      (node (ref "DD6") (pin "9") (pinfunction "4A_9") (pintype "input"))
    )
    (net (code "40") (name "/pwrOut_13") (class "Default")
      (node (ref "DD1") (pin "25") (pinfunction "GPA4_25") (pintype "bidirectional"))
      (node (ref "DD6") (pin "11") (pinfunction "5A_11") (pintype "input"))
    )
    (net (code "41") (name "/pwrOut_14") (class "Default")
      (node (ref "DD1") (pin "26") (pinfunction "GPA5_26") (pintype "bidirectional"))
      (node (ref "DD6") (pin "13") (pinfunction "6A_13") (pintype "input"))
    )
    (net (code "42") (name "/pwrOut_15") (class "Default")
      (node (ref "DD1") (pin "27") (pinfunction "GPA6_27") (pintype "bidirectional"))
      (node (ref "DD7") (pin "1") (pinfunction "1A_1") (pintype "input"))
    )
    (net (code "43") (name "/pwrOut_16") (class "Default")
      (node (ref "DD1") (pin "28") (pinfunction "GPA7_28") (pintype "bidirectional"))
      (node (ref "DD7") (pin "3") (pinfunction "2A_3") (pintype "input"))
    )
    (net (code "44") (name "GND") (class "Default")
      (node (ref "C18") (pin "1") (pinfunction "1_1") (pintype "passive"))
      (node (ref "C22") (pin "1") (pinfunction "1_1") (pintype "passive"))
      (node (ref "C23") (pin "1") (pinfunction "1_1") (pintype "passive"))
      (node (ref "C24") (pin "1") (pinfunction "1_1") (pintype "passive"))
      (node (ref "DD1") (pin "10") (pinfunction "VSS_10") (pintype "power_in"))
      (node (ref "DD5") (pin "7") (pinfunction "GND_7") (pintype "power_in"))
      (node (ref "DD6") (pin "7") (pinfunction "GND_7") (pintype "power_in"))
      (node (ref "DD7") (pin "7") (pinfunction "GND_7") (pintype "power_in"))
      (node (ref "R13") (pin "1") (pinfunction "1_1") (pintype "passive"))
      (node (ref "R14") (pin "1") (pinfunction "1_1") (pintype "passive"))
      (node (ref "R15") (pin "1") (pinfunction "1_1") (pintype "passive"))
      (node (ref "R18") (pin "1") (pinfunction "1_1") (pintype "passive"))
      (node (ref "R185") (pin "1") (pinfunction "1_1") (pintype "passive"))
      (node (ref "R21") (pin "1") (pinfunction "1_1") (pintype "passive"))
      (node (ref "R24") (pin "1") (pinfunction "1_1") (pintype "passive"))
      (node (ref "R27") (pin "1") (pinfunction "1_1") (pintype "passive"))
      (node (ref "R30") (pin "1") (pinfunction "1_1") (pintype "passive"))
      (node (ref "R33") (pin "1") (pinfunction "1_1") (pintype "passive"))
      (node (ref "R36") (pin "1") (pinfunction "1_1") (pintype "passive"))
      (node (ref "R39") (pin "1") (pinfunction "1_1") (pintype "passive"))
      (node (ref "R42") (pin "1") (pinfunction "1_1") (pintype "passive"))
      (node (ref "R45") (pin "1") (pinfunction "1_1") (pintype "passive"))
      (node (ref "R48") (pin "1") (pinfunction "1_1") (pintype "passive"))
      (node (ref "R51") (pin "1") (pinfunction "1_1") (pintype "passive"))
      (node (ref "R54") (pin "1") (pinfunction "1_1") (pintype "passive"))
      (node (ref "R57") (pin "1") (pinfunction "1_1") (pintype "passive"))
      (node (ref "R60") (pin "1") (pinfunction "1_1") (pintype "passive"))
      (node (ref "R63") (pin "1") (pinfunction "1_1") (pintype "passive"))
      (node (ref "VT10") (pin "3") (pinfunction "S_3") (pintype "passive"))
      (node (ref "VT11") (pin "3") (pinfunction "S_3") (pintype "passive"))
      (node (ref "VT12") (pin "3") (pinfunction "S_3") (pintype "passive"))
      (node (ref "VT13") (pin "3") (pinfunction "S_3") (pintype "passive"))
      (node (ref "VT14") (pin "3") (pinfunction "S_3") (pintype "passive"))
      (node (ref "VT15") (pin "3") (pinfunction "S_3") (pintype "passive"))
      (node (ref "VT16") (pin "3") (pinfunction "S_3") (pintype "passive"))
      (node (ref "VT17") (pin "3") (pinfunction "S_3") (pintype "passive"))
      (node (ref "VT18") (pin "3") (pinfunction "S_3") (pintype "passive"))
      (node (ref "VT19") (pin "3") (pinfunction "S_3") (pintype "passive"))
      (node (ref "VT4") (pin "3") (pinfunction "S_3") (pintype "passive"))
      (node (ref "VT5") (pin "3") (pinfunction "S_3") (pintype "passive"))
      (node (ref "VT6") (pin "3") (pinfunction "S_3") (pintype "passive"))
      (node (ref "VT7") (pin "3") (pinfunction "S_3") (pintype "passive"))
      (node (ref "VT8") (pin "3") (pinfunction "S_3") (pintype "passive"))
      (node (ref "VT9") (pin "3") (pinfunction "S_3") (pintype "passive"))
      (node (ref "XP3") (pin "9") (pinfunction "9_9") (pintype "passive"))
    )
    (net (code "45") (name "Net-(DD1-A0)") (class "Default")
      (node (ref "DD1") (pin "15") (pinfunction "A0_15") (pintype "input"))
      (node (ref "R13") (pin "2") (pinfunction "2_2") (pintype "passive"))
    )
    (net (code "46") (name "Net-(DD1-A1)") (class "Default")
      (node (ref "DD1") (pin "16") (pinfunction "A1_16") (pintype "input"))
      (node (ref "R14") (pin "2") (pinfunction "2_2") (pintype "passive"))
    )
    (net (code "47") (name "Net-(DD1-A2)") (class "Default")
      (node (ref "DD1") (pin "17") (pinfunction "A2_17") (pintype "input"))
      (node (ref "R15") (pin "2") (pinfunction "2_2") (pintype "passive"))
    )
    (net (code "48") (name "Net-(DD7-3A)") (class "Default")
      (node (ref "DD7") (pin "5") (pinfunction "3A_5") (pintype "input"))
      (node (ref "DD7") (pin "9") (pinfunction "4A_9") (pintype "input"))
      (node (ref "R186") (pin "2") (pinfunction "2_2") (pintype "passive"))
    )
    (net (code "49") (name "Net-(VT4-D)") (class "Default")
      (node (ref "VD5") (pin "1") (pinfunction "1_1") (pintype "passive"))
      (node (ref "VT4") (pin "2") (pinfunction "D_2") (pintype "passive"))
      (node (ref "XS1") (pin "1") (pinfunction "1_1") (pintype "passive"))
    )
    (net (code "50") (name "Net-(VT4-G)") (class "Default")
      (node (ref "R16") (pin "2") (pinfunction "2_2") (pintype "passive"))
      (node (ref "R18") (pin "2") (pinfunction "2_2") (pintype "passive"))
      (node (ref "VT4") (pin "1") (pinfunction "G_1") (pintype "passive"))
    )
    (net (code "51") (name "Net-(VT5-D)") (class "Default")
      (node (ref "VD6") (pin "1") (pinfunction "1_1") (pintype "passive"))
      (node (ref "VT5") (pin "2") (pinfunction "D_2") (pintype "passive"))
      (node (ref "XS1") (pin "2") (pinfunction "2_2") (pintype "passive"))
    )
    (net (code "52") (name "Net-(VT5-G)") (class "Default")
      (node (ref "R19") (pin "2") (pinfunction "2_2") (pintype "passive"))
      (node (ref "R21") (pin "2") (pinfunction "2_2") (pintype "passive"))
      (node (ref "VT5") (pin "1") (pinfunction "G_1") (pintype "passive"))
    )
    (net (code "53") (name "Net-(VT6-D)") (class "Default")
      (node (ref "VD7") (pin "1") (pinfunction "1_1") (pintype "passive"))
      (node (ref "VT6") (pin "2") (pinfunction "D_2") (pintype "passive"))
      (node (ref "XS1") (pin "3") (pinfunction "3_3") (pintype "passive"))
    )
    (net (code "54") (name "Net-(VT6-G)") (class "Default")
      (node (ref "R22") (pin "2") (pinfunction "2_2") (pintype "passive"))
      (node (ref "R24") (pin "2") (pinfunction "2_2") (pintype "passive"))
      (node (ref "VT6") (pin "1") (pinfunction "G_1") (pintype "passive"))
    )
    (net (code "55") (name "Net-(VT7-D)") (class "Default")
      (node (ref "VD8") (pin "1") (pinfunction "1_1") (pintype "passive"))
      (node (ref "VT7") (pin "2") (pinfunction "D_2") (pintype "passive"))
      (node (ref "XS1") (pin "4") (pinfunction "4_4") (pintype "passive"))
    )
    (net (code "56") (name "Net-(VT7-G)") (class "Default")
      (node (ref "R25") (pin "2") (pinfunction "2_2") (pintype "passive"))
      (node (ref "R27") (pin "2") (pinfunction "2_2") (pintype "passive"))
      (node (ref "VT7") (pin "1") (pinfunction "G_1") (pintype "passive"))
    )
    (net (code "57") (name "Net-(VT8-D)") (class "Default")
      (node (ref "VD9") (pin "1") (pinfunction "1_1") (pintype "passive"))
      (node (ref "VT8") (pin "2") (pinfunction "D_2") (pintype "passive"))
      (node (ref "XS1") (pin "5") (pinfunction "5_5") (pintype "passive"))
    )
    (net (code "58") (name "Net-(VT8-G)") (class "Default")
      (node (ref "R28") (pin "2") (pinfunction "2_2") (pintype "passive"))
      (node (ref "R30") (pin "2") (pinfunction "2_2") (pintype "passive"))
      (node (ref "VT8") (pin "1") (pinfunction "G_1") (pintype "passive"))
    )
    (net (code "59") (name "Net-(VT9-D)") (class "Default")
      (node (ref "VD10") (pin "1") (pinfunction "1_1") (pintype "passive"))
      (node (ref "VT9") (pin "2") (pinfunction "D_2") (pintype "passive"))
      (node (ref "XS1") (pin "6") (pinfunction "6_6") (pintype "passive"))
    )
    (net (code "60") (name "Net-(VT9-G)") (class "Default")
      (node (ref "R31") (pin "2") (pinfunction "2_2") (pintype "passive"))
      (node (ref "R33") (pin "2") (pinfunction "2_2") (pintype "passive"))
      (node (ref "VT9") (pin "1") (pinfunction "G_1") (pintype "passive"))
    )
    (net (code "61") (name "Net-(VT10-D)") (class "Default")
      (node (ref "VD11") (pin "1") (pinfunction "1_1") (pintype "passive"))
      (node (ref "VT10") (pin "2") (pinfunction "D_2") (pintype "passive"))
      (node (ref "XS1") (pin "7") (pinfunction "7_7") (pintype "passive"))
    )
    (net (code "62") (name "Net-(VT10-G)") (class "Default")
      (node (ref "R34") (pin "2") (pinfunction "2_2") (pintype "passive"))
      (node (ref "R36") (pin "2") (pinfunction "2_2") (pintype "passive"))
      (node (ref "VT10") (pin "1") (pinfunction "G_1") (pintype "passive"))
    )
    (net (code "63") (name "Net-(VT11-D)") (class "Default")
      (node (ref "VD12") (pin "1") (pinfunction "1_1") (pintype "passive"))
      (node (ref "VT11") (pin "2") (pinfunction "D_2") (pintype "passive"))
      (node (ref "XS1") (pin "8") (pinfunction "8_8") (pintype "passive"))
    )
    (net (code "64") (name "Net-(VT11-G)") (class "Default")
      (node (ref "R37") (pin "2") (pinfunction "2_2") (pintype "passive"))
      (node (ref "R39") (pin "2") (pinfunction "2_2") (pintype "passive"))
      (node (ref "VT11") (pin "1") (pinfunction "G_1") (pintype "passive"))
    )
    (net (code "65") (name "Net-(VT12-D)") (class "Default")
      (node (ref "VD13") (pin "1") (pinfunction "1_1") (pintype "passive"))
      (node (ref "VT12") (pin "2") (pinfunction "D_2") (pintype "passive"))
      (node (ref "XS2") (pin "1") (pinfunction "1_1") (pintype "passive"))
    )
    (net (code "66") (name "Net-(VT12-G)") (class "Default")
      (node (ref "R40") (pin "2") (pinfunction "2_2") (pintype "passive"))
      (node (ref "R42") (pin "2") (pinfunction "2_2") (pintype "passive"))
      (node (ref "VT12") (pin "1") (pinfunction "G_1") (pintype "passive"))
    )
    (net (code "67") (name "Net-(VT13-D)") (class "Default")
      (node (ref "VD14") (pin "1") (pinfunction "1_1") (pintype "passive"))
      (node (ref "VT13") (pin "2") (pinfunction "D_2") (pintype "passive"))
      (node (ref "XS2") (pin "2") (pinfunction "2_2") (pintype "passive"))
    )
    (net (code "68") (name "Net-(VT13-G)") (class "Default")
      (node (ref "R43") (pin "2") (pinfunction "2_2") (pintype "passive"))
      (node (ref "R45") (pin "2") (pinfunction "2_2") (pintype "passive"))
      (node (ref "VT13") (pin "1") (pinfunction "G_1") (pintype "passive"))
    )
    (net (code "69") (name "Net-(VT14-D)") (class "Default")
      (node (ref "VD15") (pin "1") (pinfunction "1_1") (pintype "passive"))
      (node (ref "VT14") (pin "2") (pinfunction "D_2") (pintype "passive"))
      (node (ref "XS2") (pin "3") (pinfunction "3_3") (pintype "passive"))
    )
    (net (code "70") (name "Net-(VT14-G)") (class "Default")
      (node (ref "R46") (pin "2") (pinfunction "2_2") (pintype "passive"))
      (node (ref "R48") (pin "2") (pinfunction "2_2") (pintype "passive"))
      (node (ref "VT14") (pin "1") (pinfunction "G_1") (pintype "passive"))
    )
    (net (code "71") (name "Net-(VT15-D)") (class "Default")
      (node (ref "VD16") (pin "1") (pinfunction "1_1") (pintype "passive"))
      (node (ref "VT15") (pin "2") (pinfunction "D_2") (pintype "passive"))
      (node (ref "XS2") (pin "4") (pinfunction "4_4") (pintype "passive"))
    )
    (net (code "72") (name "Net-(VT15-G)") (class "Default")
      (node (ref "R49") (pin "2") (pinfunction "2_2") (pintype "passive"))
      (node (ref "R51") (pin "2") (pinfunction "2_2") (pintype "passive"))
      (node (ref "VT15") (pin "1") (pinfunction "G_1") (pintype "passive"))
    )
    (net (code "73") (name "Net-(VT16-D)") (class "Default")
      (node (ref "VD17") (pin "1") (pinfunction "1_1") (pintype "passive"))
      (node (ref "VT16") (pin "2") (pinfunction "D_2") (pintype "passive"))
      (node (ref "XS2") (pin "5") (pinfunction "5_5") (pintype "passive"))
    )
    (net (code "74") (name "Net-(VT16-G)") (class "Default")
      (node (ref "R52") (pin "2") (pinfunction "2_2") (pintype "passive"))
      (node (ref "R54") (pin "2") (pinfunction "2_2") (pintype "passive"))
      (node (ref "VT16") (pin "1") (pinfunction "G_1") (pintype "passive"))
    )
    (net (code "75") (name "Net-(VT17-D)") (class "Default")
      (node (ref "VD18") (pin "1") (pinfunction "1_1") (pintype "passive"))
      (node (ref "VT17") (pin "2") (pinfunction "D_2") (pintype "passive"))
      (node (ref "XS2") (pin "6") (pinfunction "6_6") (pintype "passive"))
    )
    (net (code "76") (name "Net-(VT17-G)") (class "Default")
      (node (ref "R55") (pin "2") (pinfunction "2_2") (pintype "passive"))
      (node (ref "R57") (pin "2") (pinfunction "2_2") (pintype "passive"))
      (node (ref "VT17") (pin "1") (pinfunction "G_1") (pintype "passive"))
    )
    (net (code "77") (name "Net-(VT18-D)") (class "Default")
      (node (ref "VD19") (pin "1") (pinfunction "1_1") (pintype "passive"))
      (node (ref "VT18") (pin "2") (pinfunction "D_2") (pintype "passive"))
      (node (ref "XS2") (pin "7") (pinfunction "7_7") (pintype "passive"))
    )
    (net (code "78") (name "Net-(VT18-G)") (class "Default")
      (node (ref "R58") (pin "2") (pinfunction "2_2") (pintype "passive"))
      (node (ref "R60") (pin "2") (pinfunction "2_2") (pintype "passive"))
      (node (ref "VT18") (pin "1") (pinfunction "G_1") (pintype "passive"))
    )
    (net (code "79") (name "Net-(VT19-D)") (class "Default")
      (node (ref "VD20") (pin "1") (pinfunction "1_1") (pintype "passive"))
      (node (ref "VT19") (pin "2") (pinfunction "D_2") (pintype "passive"))
      (node (ref "XS2") (pin "8") (pinfunction "8_8") (pintype "passive"))
    )
    (net (code "80") (name "Net-(VT19-G)") (class "Default")
      (node (ref "R61") (pin "2") (pinfunction "2_2") (pintype "passive"))
      (node (ref "R63") (pin "2") (pinfunction "2_2") (pintype "passive"))
      (node (ref "VT19") (pin "1") (pinfunction "G_1") (pintype "passive"))
    )
    (net (code "81") (name "unconnected-(DD1-INTA-Pad20)") (class "Default")
      (node (ref "DD1") (pin "20") (pinfunction "INTA_20") (pintype "output"))
    )
    (net (code "82") (name "unconnected-(DD1-INTB-Pad19)") (class "Default")
      (node (ref "DD1") (pin "19") (pinfunction "INTB_19") (pintype "output"))
    )
    (net (code "83") (name "unconnected-(DD7-3Y-Pad6)") (class "Default")
      (node (ref "DD7") (pin "6") (pinfunction "3Y_6") (pintype "output"))
    )
    (net (code "84") (name "unconnected-(DD7-4Y-Pad8)") (class "Default")
      (node (ref "DD7") (pin "8") (pinfunction "4Y_8") (pintype "output"))
    )
    (net (code "85") (name "unconnected-(XP3-Pad1)") (class "Default")
      (node (ref "XP3") (pin "1") (pinfunction "1_1") (pintype "passive"))
    )
  )
)
